# Micro_Bit_Control_Bit.net
KiCad netlist of a schematic drawn in EAGLE
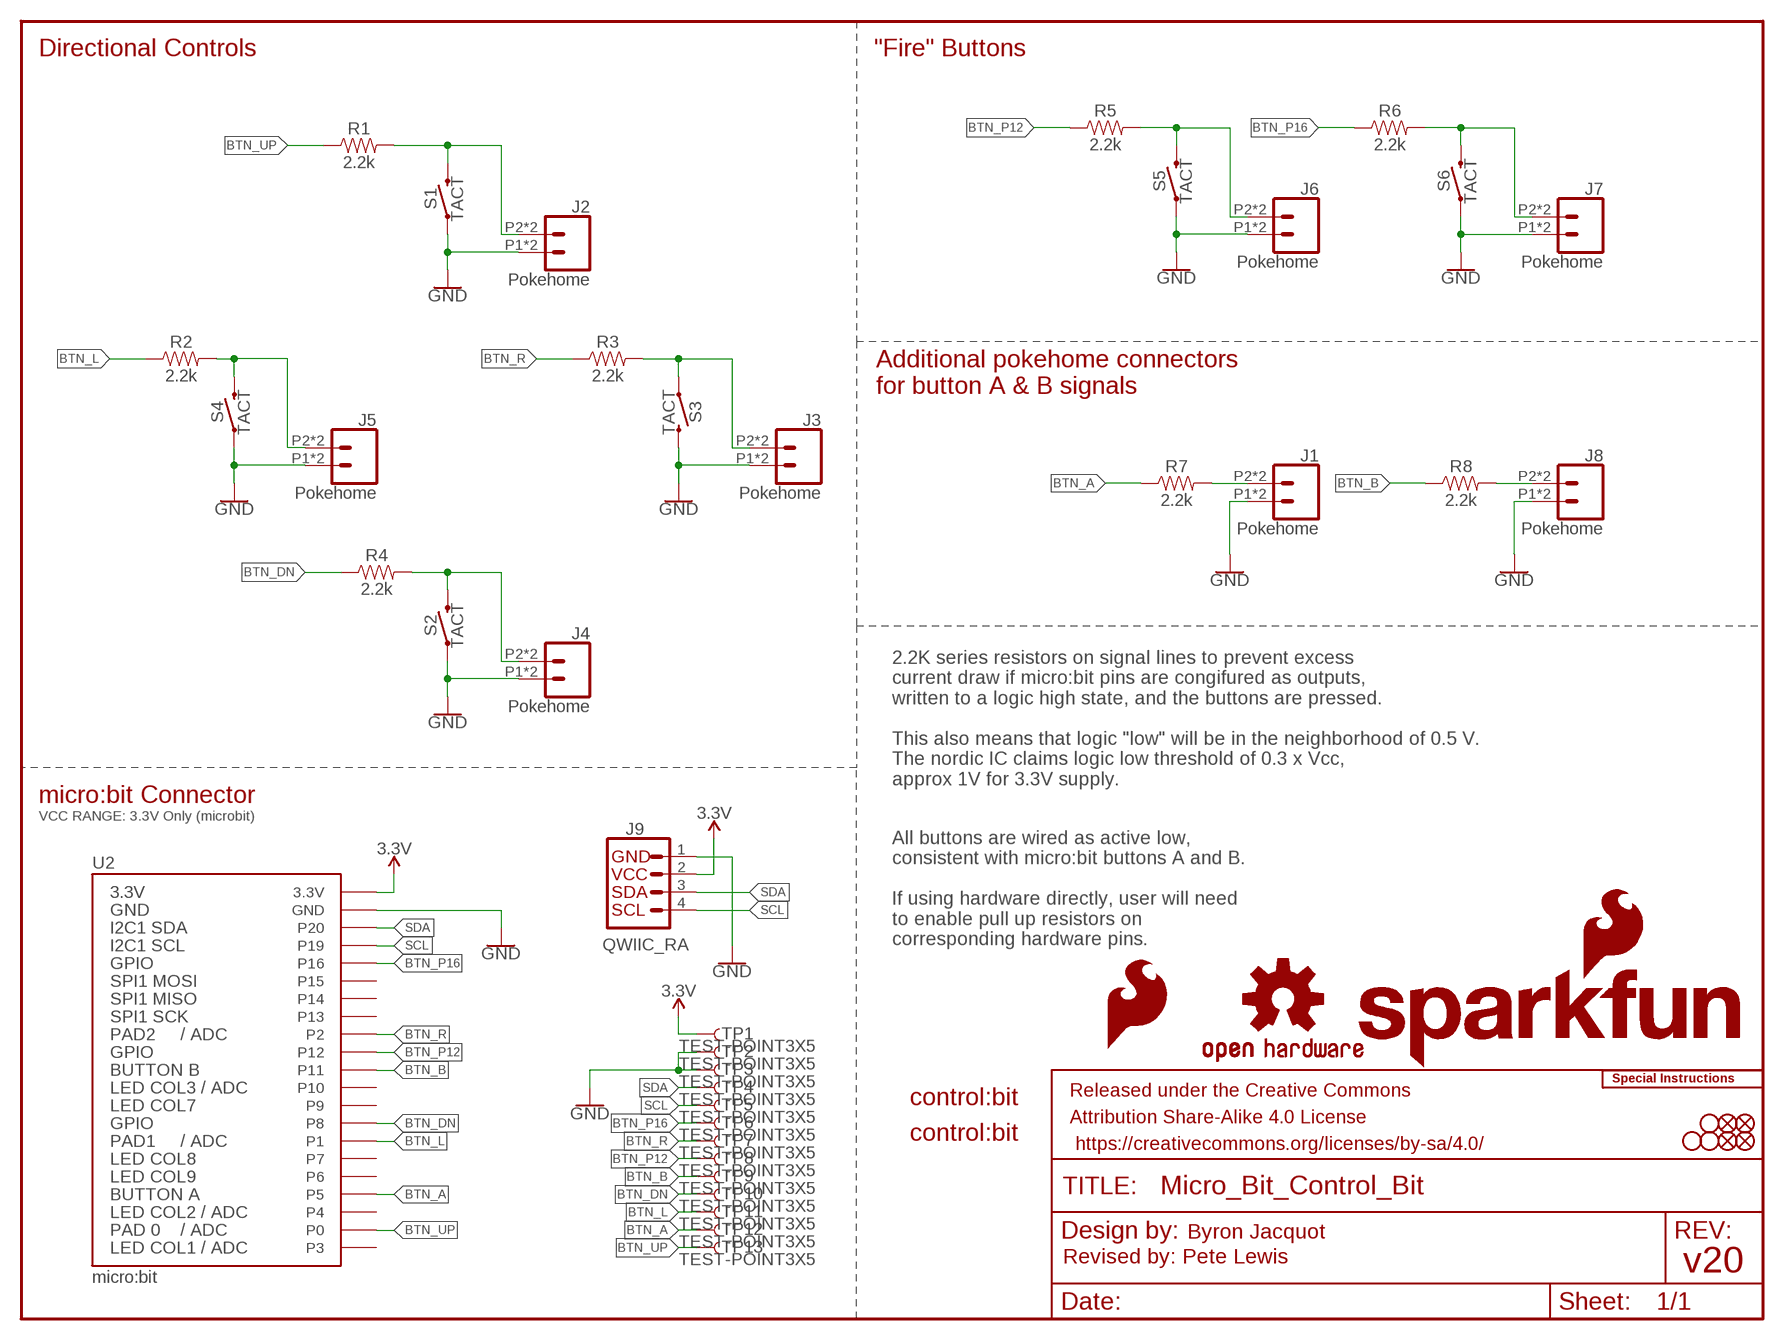
[diagram p0: schematic, sheet 1]

(export (version "E")
  (design (tool "Eeschema 10.0.6"))
  (components
    (comp (ref "FD1")
      (value "FIDUCIALUFIDUCIAL")
      (footprint "eagle-import:FIDUCIAL-MICRO")
      (libsource (lib "eagle-import") (part "FIDUCIALUFIDUCIAL"))
    )
    (comp (ref "FD2")
      (value "FIDUCIALUFIDUCIAL")
      (footprint "eagle-import:FIDUCIAL-MICRO")
      (libsource (lib "eagle-import") (part "FIDUCIALUFIDUCIAL"))
    )
    (comp (ref "FD3")
      (value "FIDUCIALUFIDUCIAL")
      (footprint "eagle-import:FIDUCIAL-MICRO")
      (libsource (lib "eagle-import") (part "FIDUCIALUFIDUCIAL"))
    )
    (comp (ref "FD4")
      (value "FIDUCIALUFIDUCIAL")
      (footprint "eagle-import:FIDUCIAL-MICRO")
      (libsource (lib "eagle-import") (part "FIDUCIALUFIDUCIAL"))
    )
    (comp (ref "FRAME1")
      (value "FRAME-LETTER")
      (footprint "eagle-import:CREATIVE_COMMONS")
      (libsource (lib "eagle-import") (part "FRAME-LETTER"))
    )
    (comp (ref "H1")
      (value "STAND-OFF")
      (footprint "eagle-import:STAND-OFF")
      (libsource (lib "eagle-import") (part "STAND-OFF"))
    )
    (comp (ref "H2")
      (value "STAND-OFF")
      (footprint "eagle-import:STAND-OFF")
      (libsource (lib "eagle-import") (part "STAND-OFF"))
    )
    (comp (ref "H3")
      (value "STAND-OFF")
      (footprint "eagle-import:STAND-OFF")
      (libsource (lib "eagle-import") (part "STAND-OFF"))
    )
    (comp (ref "J1")
      (value "Pokehome")
      (footprint "eagle-import:1X02_POKEHOME")
      (libsource (lib "eagle-import") (part "CONN_02SMALL_POKEHOME"))
    )
    (comp (ref "J2")
      (value "Pokehome")
      (footprint "eagle-import:1X02_POKEHOME")
      (libsource (lib "eagle-import") (part "CONN_02SMALL_POKEHOME"))
    )
    (comp (ref "J3")
      (value "Pokehome")
      (footprint "eagle-import:1X02_POKEHOME")
      (libsource (lib "eagle-import") (part "CONN_02SMALL_POKEHOME"))
    )
    (comp (ref "J4")
      (value "Pokehome")
      (footprint "eagle-import:1X02_POKEHOME")
      (libsource (lib "eagle-import") (part "CONN_02SMALL_POKEHOME"))
    )
    (comp (ref "J5")
      (value "Pokehome")
      (footprint "eagle-import:1X02_POKEHOME")
      (libsource (lib "eagle-import") (part "CONN_02SMALL_POKEHOME"))
    )
    (comp (ref "J6")
      (value "Pokehome")
      (footprint "eagle-import:1X02_POKEHOME")
      (libsource (lib "eagle-import") (part "CONN_02SMALL_POKEHOME"))
    )
    (comp (ref "J7")
      (value "Pokehome")
      (footprint "eagle-import:1X02_POKEHOME")
      (libsource (lib "eagle-import") (part "CONN_02SMALL_POKEHOME"))
    )
    (comp (ref "J8")
      (value "Pokehome")
      (footprint "eagle-import:1X02_POKEHOME")
      (libsource (lib "eagle-import") (part "CONN_02SMALL_POKEHOME"))
    )
    (comp (ref "J9")
      (value "QWIIC_RA")
      (footprint "eagle-import:JST04_1MM_RA")
      (libsource (lib "eagle-import") (part "QWIIC_CONNECTORJS-1MM"))
    )
    (comp (ref "LOGO1")
      (value "SFE_LOGO_FLAME.2_INCH")
      (footprint "eagle-import:SFE_LOGO_FLAME_.2")
      (libsource (lib "eagle-import") (part "SFE_LOGO_FLAME.2_INCH"))
    )
    (comp (ref "LOGO2")
      (value "OSHW-LOGOL")
      (footprint "eagle-import:OSHW-LOGO-L")
      (libsource (lib "eagle-import") (part "OSHW-LOGOL"))
    )
    (comp (ref "LOGO3")
      (value "SFE_LOGO_NAME_FLAME.3_INCH")
      (footprint "eagle-import:SFE_LOGO_NAME_FLAME_.3")
      (libsource (lib "eagle-import") (part "SFE_LOGO_NAME_FLAME.3_INCH"))
    )
    (comp (ref "R1")
      (value "2.2k")
      (footprint "eagle-import:0603")
      (libsource (lib "eagle-import") (part "2.2KOHM-0603-1/10W-1%"))
    )
    (comp (ref "R2")
      (value "2.2k")
      (footprint "eagle-import:0603")
      (libsource (lib "eagle-import") (part "2.2KOHM-0603-1/10W-1%"))
    )
    (comp (ref "R3")
      (value "2.2k")
      (footprint "eagle-import:0603")
      (libsource (lib "eagle-import") (part "2.2KOHM-0603-1/10W-1%"))
    )
    (comp (ref "R4")
      (value "2.2k")
      (footprint "eagle-import:0603")
      (libsource (lib "eagle-import") (part "2.2KOHM-0603-1/10W-1%"))
    )
    (comp (ref "R5")
      (value "2.2k")
      (footprint "eagle-import:0603")
      (libsource (lib "eagle-import") (part "2.2KOHM-0603-1/10W-1%"))
    )
    (comp (ref "R6")
      (value "2.2k")
      (footprint "eagle-import:0603")
      (libsource (lib "eagle-import") (part "2.2KOHM-0603-1/10W-1%"))
    )
    (comp (ref "R7")
      (value "2.2k")
      (footprint "eagle-import:0603")
      (libsource (lib "eagle-import") (part "2.2KOHM-0603-1/10W-1%"))
    )
    (comp (ref "R8")
      (value "2.2k")
      (footprint "eagle-import:0603")
      (libsource (lib "eagle-import") (part "2.2KOHM-0603-1/10W-1%"))
    )
    (comp (ref "S1")
      (value "TACT")
      (footprint "eagle-import:TACTILE_SWITCH_SMD_12MM")
      (libsource (lib "eagle-import") (part "MOMENTARY-SWITCH-SPST-SMD-12MM"))
    )
    (comp (ref "S2")
      (value "TACT")
      (footprint "eagle-import:TACTILE_SWITCH_SMD_12MM")
      (libsource (lib "eagle-import") (part "MOMENTARY-SWITCH-SPST-SMD-12MM"))
    )
    (comp (ref "S3")
      (value "TACT")
      (footprint "eagle-import:TACTILE_SWITCH_SMD_12MM")
      (libsource (lib "eagle-import") (part "MOMENTARY-SWITCH-SPST-SMD-12MM"))
    )
    (comp (ref "S4")
      (value "TACT")
      (footprint "eagle-import:TACTILE_SWITCH_SMD_12MM")
      (libsource (lib "eagle-import") (part "MOMENTARY-SWITCH-SPST-SMD-12MM"))
    )
    (comp (ref "S5")
      (value "TACT")
      (footprint "eagle-import:TACTILE_SWITCH_SMD_12MM")
      (libsource (lib "eagle-import") (part "MOMENTARY-SWITCH-SPST-SMD-12MM"))
    )
    (comp (ref "S6")
      (value "TACT")
      (footprint "eagle-import:TACTILE_SWITCH_SMD_12MM")
      (libsource (lib "eagle-import") (part "MOMENTARY-SWITCH-SPST-SMD-12MM"))
    )
    (comp (ref "TP1")
      (value "TEST-POINT3X5")
      (footprint "eagle-import:PAD.03X.05")
      (libsource (lib "eagle-import") (part "TEST-POINT3X5"))
    )
    (comp (ref "TP2")
      (value "TEST-POINT3X5")
      (footprint "eagle-import:PAD.03X.05")
      (libsource (lib "eagle-import") (part "TEST-POINT3X5"))
    )
    (comp (ref "TP3")
      (value "TEST-POINT3X5")
      (footprint "eagle-import:PAD.03X.05")
      (libsource (lib "eagle-import") (part "TEST-POINT3X5"))
    )
    (comp (ref "TP4")
      (value "TEST-POINT3X5")
      (footprint "eagle-import:PAD.03X.05")
      (libsource (lib "eagle-import") (part "TEST-POINT3X5"))
    )
    (comp (ref "TP5")
      (value "TEST-POINT3X5")
      (footprint "eagle-import:PAD.03X.05")
      (libsource (lib "eagle-import") (part "TEST-POINT3X5"))
    )
    (comp (ref "TP6")
      (value "TEST-POINT3X5")
      (footprint "eagle-import:PAD.03X.05")
      (libsource (lib "eagle-import") (part "TEST-POINT3X5"))
    )
    (comp (ref "TP7")
      (value "TEST-POINT3X5")
      (footprint "eagle-import:PAD.03X.05")
      (libsource (lib "eagle-import") (part "TEST-POINT3X5"))
    )
    (comp (ref "TP8")
      (value "TEST-POINT3X5")
      (footprint "eagle-import:PAD.03X.05")
      (libsource (lib "eagle-import") (part "TEST-POINT3X5"))
    )
    (comp (ref "TP9")
      (value "TEST-POINT3X5")
      (footprint "eagle-import:PAD.03X.05")
      (libsource (lib "eagle-import") (part "TEST-POINT3X5"))
    )
    (comp (ref "TP10")
      (value "TEST-POINT3X5")
      (footprint "eagle-import:PAD.03X.05")
      (libsource (lib "eagle-import") (part "TEST-POINT3X5"))
    )
    (comp (ref "TP11")
      (value "TEST-POINT3X5")
      (footprint "eagle-import:PAD.03X.05")
      (libsource (lib "eagle-import") (part "TEST-POINT3X5"))
    )
    (comp (ref "TP12")
      (value "TEST-POINT3X5")
      (footprint "eagle-import:PAD.03X.05")
      (libsource (lib "eagle-import") (part "TEST-POINT3X5"))
    )
    (comp (ref "TP13")
      (value "TEST-POINT3X5")
      (footprint "eagle-import:PAD.03X.05")
      (libsource (lib "eagle-import") (part "TEST-POINT3X5"))
    )
    (comp (ref "U$1")
      (value "SPECIAL_INSTRUCTIONS-ORDERING")
      (footprint "eagle-import:ORDERING_INSTRUCTIONS")
      (libsource (lib "eagle-import") (part "SPECIAL_INSTRUCTIONS-ORDERING"))
    )
    (comp (ref "U$4")
      (value "LOGO-CONTROLBIT")
      (footprint "eagle-import:LOGO-CONTROLBIT")
      (libsource (lib "eagle-import") (part "LOGO-CONTROLBIT"))
    )
    (comp (ref "U$5")
      (value "LOGO-CONTROLBIT")
      (footprint "eagle-import:LOGO-CONTROLBIT")
      (libsource (lib "eagle-import") (part "LOGO-CONTROLBIT"))
    )
    (comp (ref "U2")
      (value "micro:bit")
      (footprint "eagle-import:MICRO_BIT-RA_SMD")
      (libsource (lib "eagle-import") (part "MICRO{colon}BIT?_RA"))
    )
  )
  (nets
    (net (code "1") (name "3.3V") (class "Default")
      (node (ref "J9") (pin "2") (pinfunction "2_2") (pintype "power_in"))
      (node (ref "TP1") (pin "P$1") (pinfunction "1_P$1") (pintype "bidirectional"))
      (node (ref "U2") (pin "P$27") (pinfunction "3.3V_P$27") (pintype "bidirectional"))
      (node (ref "U2") (pin "P$28") (pinfunction "3.3V_P$28") (pintype "bidirectional"))
      (node (ref "U2") (pin "P$29") (pinfunction "3.3V_P$29") (pintype "bidirectional"))
      (node (ref "U2") (pin "P$30") (pinfunction "3.3V_P$30") (pintype "bidirectional"))
      (node (ref "U2") (pin "P$31") (pinfunction "3.3V_P$31") (pintype "bidirectional"))
      (node (ref "U2") (pin "P$32") (pinfunction "3.3V_P$32") (pintype "bidirectional"))
    )
    (net (code "2") (name "BTN_A") (class "Default")
      (node (ref "R7") (pin "1") (pinfunction "1_1") (pintype "passive"))
      (node (ref "TP12") (pin "P$1") (pinfunction "1_P$1") (pintype "bidirectional"))
      (node (ref "U2") (pin "P$7") (pinfunction "P5_P$7") (pintype "bidirectional"))
    )
    (net (code "3") (name "BTN_B") (class "Default")
      (node (ref "R8") (pin "1") (pinfunction "1_1") (pintype "passive"))
      (node (ref "TP9") (pin "P$1") (pinfunction "1_P$1") (pintype "bidirectional"))
      (node (ref "U2") (pin "P$17") (pinfunction "P11_P$17") (pintype "bidirectional"))
    )
    (net (code "4") (name "BTN_DN") (class "Default")
      (node (ref "R4") (pin "1") (pinfunction "1_1") (pintype "passive"))
      (node (ref "TP10") (pin "P$1") (pinfunction "1_P$1") (pintype "bidirectional"))
      (node (ref "U2") (pin "P$14") (pinfunction "P8_P$14") (pintype "bidirectional"))
    )
    (net (code "5") (name "BTN_L") (class "Default")
      (node (ref "R2") (pin "1") (pinfunction "1_1") (pintype "passive"))
      (node (ref "TP11") (pin "P$1") (pinfunction "1_P$1") (pintype "bidirectional"))
      (node (ref "U2") (pin "P$10") (pinfunction "P1_P$10") (pintype "bidirectional"))
      (node (ref "U2") (pin "P$11") (pinfunction "P1_P$11") (pintype "bidirectional"))
      (node (ref "U2") (pin "P$12") (pinfunction "P1_P$12") (pintype "bidirectional"))
      (node (ref "U2") (pin "P$13") (pinfunction "P1_P$13") (pintype "bidirectional"))
    )
    (net (code "6") (name "BTN_P12") (class "Default")
      (node (ref "R5") (pin "1") (pinfunction "1_1") (pintype "passive"))
      (node (ref "TP8") (pin "P$1") (pinfunction "1_P$1") (pintype "bidirectional"))
      (node (ref "U2") (pin "P$18") (pinfunction "P12_P$18") (pintype "bidirectional"))
    )
    (net (code "7") (name "BTN_P16") (class "Default")
      (node (ref "R6") (pin "1") (pinfunction "1_1") (pintype "passive"))
      (node (ref "TP6") (pin "P$1") (pinfunction "1_P$1") (pintype "bidirectional"))
      (node (ref "U2") (pin "P$26") (pinfunction "P16_P$26") (pintype "bidirectional"))
    )
    (net (code "8") (name "BTN_R") (class "Default")
      (node (ref "R3") (pin "1") (pinfunction "1_1") (pintype "passive"))
      (node (ref "TP7") (pin "P$1") (pinfunction "1_P$1") (pintype "bidirectional"))
      (node (ref "U2") (pin "P$19") (pinfunction "P2_P$19") (pintype "bidirectional"))
      (node (ref "U2") (pin "P$20") (pinfunction "P2_P$20") (pintype "bidirectional"))
      (node (ref "U2") (pin "P$21") (pinfunction "P2_P$21") (pintype "bidirectional"))
      (node (ref "U2") (pin "P$22") (pinfunction "P2_P$22") (pintype "bidirectional"))
    )
    (net (code "9") (name "BTN_UP") (class "Default")
      (node (ref "R1") (pin "1") (pinfunction "1_1") (pintype "passive"))
      (node (ref "TP13") (pin "P$1") (pinfunction "1_P$1") (pintype "bidirectional"))
      (node (ref "U2") (pin "P$2") (pinfunction "P0_P$2") (pintype "bidirectional"))
      (node (ref "U2") (pin "P$3") (pinfunction "P0_P$3") (pintype "bidirectional"))
      (node (ref "U2") (pin "P$4") (pinfunction "P0_P$4") (pintype "bidirectional"))
      (node (ref "U2") (pin "P$5") (pinfunction "P0_P$5") (pintype "bidirectional"))
    )
    (net (code "10") (name "GND") (class "Default")
      (node (ref "J1") (pin "P1") (pinfunction "1_P1") (pintype "passive"))
      (node (ref "J1") (pin "P3") (pinfunction "1_P3") (pintype "passive"))
      (node (ref "J2") (pin "P1") (pinfunction "1_P1") (pintype "passive"))
      (node (ref "J2") (pin "P3") (pinfunction "1_P3") (pintype "passive"))
      (node (ref "J3") (pin "P1") (pinfunction "1_P1") (pintype "passive"))
      (node (ref "J3") (pin "P3") (pinfunction "1_P3") (pintype "passive"))
      (node (ref "J4") (pin "P1") (pinfunction "1_P1") (pintype "passive"))
      (node (ref "J4") (pin "P3") (pinfunction "1_P3") (pintype "passive"))
      (node (ref "J5") (pin "P1") (pinfunction "1_P1") (pintype "passive"))
      (node (ref "J5") (pin "P3") (pinfunction "1_P3") (pintype "passive"))
      (node (ref "J6") (pin "P1") (pinfunction "1_P1") (pintype "passive"))
      (node (ref "J6") (pin "P3") (pinfunction "1_P3") (pintype "passive"))
      (node (ref "J7") (pin "P1") (pinfunction "1_P1") (pintype "passive"))
      (node (ref "J7") (pin "P3") (pinfunction "1_P3") (pintype "passive"))
      (node (ref "J8") (pin "P1") (pinfunction "1_P1") (pintype "passive"))
      (node (ref "J8") (pin "P3") (pinfunction "1_P3") (pintype "passive"))
      (node (ref "J9") (pin "1") (pinfunction "1_1") (pintype "power_in"))
      (node (ref "S1") (pin "1") (pinfunction "1_1") (pintype "passive"))
      (node (ref "S2") (pin "1") (pinfunction "1_1") (pintype "passive"))
      (node (ref "S3") (pin "3") (pinfunction "2_3") (pintype "passive"))
      (node (ref "S4") (pin "1") (pinfunction "1_1") (pintype "passive"))
      (node (ref "S5") (pin "1") (pinfunction "1_1") (pintype "passive"))
      (node (ref "S6") (pin "1") (pinfunction "1_1") (pintype "passive"))
      (node (ref "TP2") (pin "P$1") (pinfunction "1_P$1") (pintype "bidirectional"))
      (node (ref "TP3") (pin "P$1") (pinfunction "1_P$1") (pintype "bidirectional"))
      (node (ref "U2") (pin "P$35") (pinfunction "GND_P$35") (pintype "bidirectional"))
      (node (ref "U2") (pin "P$36") (pinfunction "GND_P$36") (pintype "bidirectional"))
      (node (ref "U2") (pin "P$37") (pinfunction "GND_P$37") (pintype "bidirectional"))
      (node (ref "U2") (pin "P$38") (pinfunction "GND_P$38") (pintype "bidirectional"))
      (node (ref "U2") (pin "P$39") (pinfunction "GND_P$39") (pintype "bidirectional"))
      (node (ref "U2") (pin "P$40") (pinfunction "GND_P$40") (pintype "bidirectional"))
    )
    (net (code "11") (name "Net-(J1-2-PadP2)") (class "Default")
      (node (ref "J1") (pin "P2") (pinfunction "2_P2") (pintype "passive"))
      (node (ref "J1") (pin "P4") (pinfunction "2_P4") (pintype "passive"))
      (node (ref "R7") (pin "2") (pinfunction "2_2") (pintype "passive"))
    )
    (net (code "12") (name "Net-(J3-2-PadP2)") (class "Default")
      (node (ref "J3") (pin "P2") (pinfunction "2_P2") (pintype "passive"))
      (node (ref "J3") (pin "P4") (pinfunction "2_P4") (pintype "passive"))
      (node (ref "R3") (pin "2") (pinfunction "2_2") (pintype "passive"))
      (node (ref "S3") (pin "1") (pinfunction "1_1") (pintype "passive"))
    )
    (net (code "13") (name "Net-(J8-2-PadP2)") (class "Default")
      (node (ref "J8") (pin "P2") (pinfunction "2_P2") (pintype "passive"))
      (node (ref "J8") (pin "P4") (pinfunction "2_P4") (pintype "passive"))
      (node (ref "R8") (pin "2") (pinfunction "2_2") (pintype "passive"))
    )
    (net (code "14") (name "Net-(S1-2)") (class "Default")
      (node (ref "J2") (pin "P2") (pinfunction "2_P2") (pintype "passive"))
      (node (ref "J2") (pin "P4") (pinfunction "2_P4") (pintype "passive"))
      (node (ref "R1") (pin "2") (pinfunction "2_2") (pintype "passive"))
      (node (ref "S1") (pin "3") (pinfunction "2_3") (pintype "passive"))
    )
    (net (code "15") (name "Net-(S2-2)") (class "Default")
      (node (ref "J4") (pin "P2") (pinfunction "2_P2") (pintype "passive"))
      (node (ref "J4") (pin "P4") (pinfunction "2_P4") (pintype "passive"))
      (node (ref "R4") (pin "2") (pinfunction "2_2") (pintype "passive"))
      (node (ref "S2") (pin "3") (pinfunction "2_3") (pintype "passive"))
    )
    (net (code "16") (name "Net-(S4-2)") (class "Default")
      (node (ref "J5") (pin "P2") (pinfunction "2_P2") (pintype "passive"))
      (node (ref "J5") (pin "P4") (pinfunction "2_P4") (pintype "passive"))
      (node (ref "R2") (pin "2") (pinfunction "2_2") (pintype "passive"))
      (node (ref "S4") (pin "3") (pinfunction "2_3") (pintype "passive"))
    )
    (net (code "17") (name "Net-(S5-2)") (class "Default")
      (node (ref "J6") (pin "P2") (pinfunction "2_P2") (pintype "passive"))
      (node (ref "J6") (pin "P4") (pinfunction "2_P4") (pintype "passive"))
      (node (ref "R5") (pin "2") (pinfunction "2_2") (pintype "passive"))
      (node (ref "S5") (pin "3") (pinfunction "2_3") (pintype "passive"))
    )
    (net (code "18") (name "Net-(S6-2)") (class "Default")
      (node (ref "J7") (pin "P2") (pinfunction "2_P2") (pintype "passive"))
      (node (ref "J7") (pin "P4") (pinfunction "2_P4") (pintype "passive"))
      (node (ref "R6") (pin "2") (pinfunction "2_2") (pintype "passive"))
      (node (ref "S6") (pin "3") (pinfunction "2_3") (pintype "passive"))
    )
    (net (code "19") (name "SCL") (class "Default")
      (node (ref "J9") (pin "4") (pinfunction "4_4") (pintype "passive"))
      (node (ref "TP5") (pin "P$1") (pinfunction "1_P$1") (pintype "bidirectional"))
      (node (ref "U2") (pin "P$33") (pinfunction "P19_P$33") (pintype "bidirectional"))
    )
    (net (code "20") (name "SDA") (class "Default")
      (node (ref "J9") (pin "3") (pinfunction "3_3") (pintype "passive"))
      (node (ref "TP4") (pin "P$1") (pinfunction "1_P$1") (pintype "bidirectional"))
      (node (ref "U2") (pin "P$34") (pinfunction "P20_P$34") (pintype "bidirectional"))
    )
    (net (code "21") (name "unconnected-(U2-P3-PadP$1)") (class "Default")
      (node (ref "U2") (pin "P$1") (pinfunction "P3_P$1") (pintype "bidirectional"))
    )
    (net (code "22") (name "unconnected-(U2-P4-PadP$6)") (class "Default")
      (node (ref "U2") (pin "P$6") (pinfunction "P4_P$6") (pintype "bidirectional"))
    )
    (net (code "23") (name "unconnected-(U2-P6-PadP$8)") (class "Default")
      (node (ref "U2") (pin "P$8") (pinfunction "P6_P$8") (pintype "bidirectional"))
    )
    (net (code "24") (name "unconnected-(U2-P7-PadP$9)") (class "Default")
      (node (ref "U2") (pin "P$9") (pinfunction "P7_P$9") (pintype "bidirectional"))
    )
    (net (code "25") (name "unconnected-(U2-P9-PadP$15)") (class "Default")
      (node (ref "U2") (pin "P$15") (pinfunction "P9_P$15") (pintype "bidirectional"))
    )
    (net (code "26") (name "unconnected-(U2-P10-PadP$16)") (class "Default")
      (node (ref "U2") (pin "P$16") (pinfunction "P10_P$16") (pintype "bidirectional"))
    )
    (net (code "27") (name "unconnected-(U2-P13-PadP$23)") (class "Default")
      (node (ref "U2") (pin "P$23") (pinfunction "P13_P$23") (pintype "bidirectional"))
    )
    (net (code "28") (name "unconnected-(U2-P14-PadP$24)") (class "Default")
      (node (ref "U2") (pin "P$24") (pinfunction "P14_P$24") (pintype "bidirectional"))
    )
    (net (code "29") (name "unconnected-(U2-P15-PadP$25)") (class "Default")
      (node (ref "U2") (pin "P$25") (pinfunction "P15_P$25") (pintype "bidirectional"))
    )
  )
)
